# ChairControl.net
KiCad netlist of a schematic drawn in EAGLE
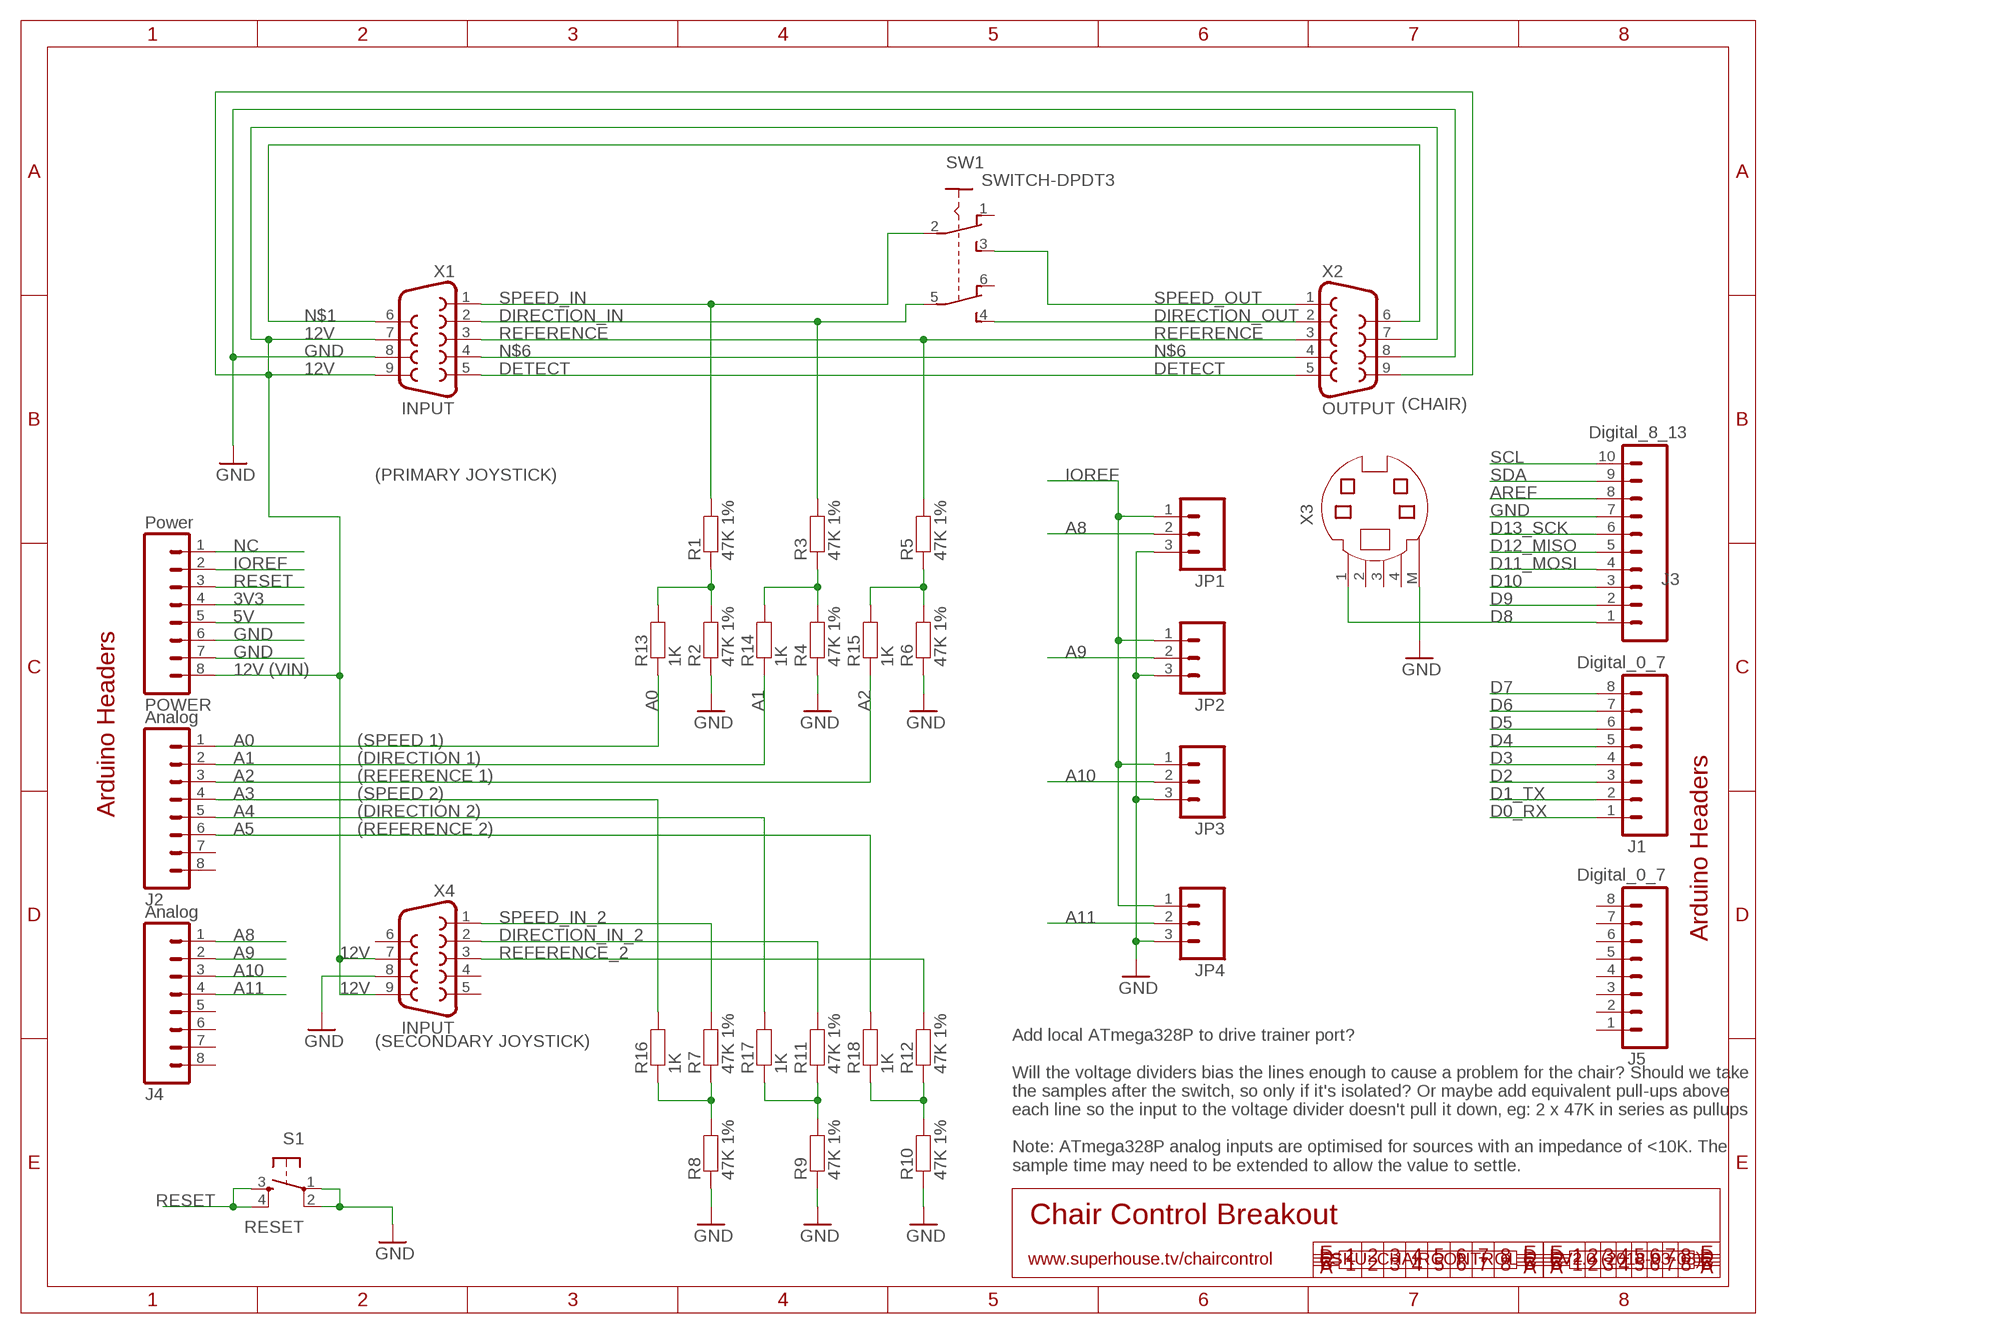
[diagram p0: schematic, sheet 1]

(export (version "E")
  (design (tool "Eeschema 10.0.6"))
  (components
    (comp (ref "J1")
      (value "Digital_0_7")
      (footprint "eagle-import:1X08")
      (libsource (lib "eagle-import") (part "M08"))
    )
    (comp (ref "J2")
      (value "Analog")
      (footprint "eagle-import:1X08")
      (libsource (lib "eagle-import") (part "M08PTH"))
    )
    (comp (ref "J3")
      (value "Digital_8_13")
      (footprint "eagle-import:1X10")
      (libsource (lib "eagle-import") (part "M100.1"))
    )
    (comp (ref "J4")
      (value "Analog")
      (footprint "eagle-import:1X08")
      (libsource (lib "eagle-import") (part "M08PTH"))
    )
    (comp (ref "J5")
      (value "Digital_0_7")
      (footprint "eagle-import:1X08")
      (libsource (lib "eagle-import") (part "M08"))
    )
    (comp (ref "JP1")
      (value "M03PTH")
      (footprint "eagle-import:1X03")
      (libsource (lib "eagle-import") (part "M03PTH"))
    )
    (comp (ref "JP2")
      (value "M03PTH")
      (footprint "eagle-import:1X03")
      (libsource (lib "eagle-import") (part "M03PTH"))
    )
    (comp (ref "JP3")
      (value "M03PTH")
      (footprint "eagle-import:1X03")
      (libsource (lib "eagle-import") (part "M03PTH"))
    )
    (comp (ref "JP4")
      (value "M03PTH")
      (footprint "eagle-import:1X03")
      (libsource (lib "eagle-import") (part "M03PTH"))
    )
    (comp (ref "POWER")
      (value "Power")
      (footprint "eagle-import:1X08")
      (libsource (lib "eagle-import") (part "freetronics-original_M08"))
    )
    (comp (ref "R1")
      (value "47K 1%")
      (footprint "eagle-import:0603")
      (libsource (lib "eagle-import") (part "RESISTOR0603"))
    )
    (comp (ref "R2")
      (value "47K 1%")
      (footprint "eagle-import:0603")
      (libsource (lib "eagle-import") (part "RESISTOR0603"))
    )
    (comp (ref "R3")
      (value "47K 1%")
      (footprint "eagle-import:0603")
      (libsource (lib "eagle-import") (part "RESISTOR0603"))
    )
    (comp (ref "R4")
      (value "47K 1%")
      (footprint "eagle-import:0603")
      (libsource (lib "eagle-import") (part "RESISTOR0603"))
    )
    (comp (ref "R5")
      (value "47K 1%")
      (footprint "eagle-import:0603")
      (libsource (lib "eagle-import") (part "RESISTOR0603"))
    )
    (comp (ref "R6")
      (value "47K 1%")
      (footprint "eagle-import:0603")
      (libsource (lib "eagle-import") (part "RESISTOR0603"))
    )
    (comp (ref "R7")
      (value "47K 1%")
      (footprint "eagle-import:0603")
      (libsource (lib "eagle-import") (part "RESISTOR0603"))
    )
    (comp (ref "R8")
      (value "47K 1%")
      (footprint "eagle-import:0603")
      (libsource (lib "eagle-import") (part "RESISTOR0603"))
    )
    (comp (ref "R9")
      (value "47K 1%")
      (footprint "eagle-import:0603")
      (libsource (lib "eagle-import") (part "RESISTOR0603"))
    )
    (comp (ref "R10")
      (value "47K 1%")
      (footprint "eagle-import:0603")
      (libsource (lib "eagle-import") (part "RESISTOR0603"))
    )
    (comp (ref "R11")
      (value "47K 1%")
      (footprint "eagle-import:0603")
      (libsource (lib "eagle-import") (part "RESISTOR0603"))
    )
    (comp (ref "R12")
      (value "47K 1%")
      (footprint "eagle-import:0603")
      (libsource (lib "eagle-import") (part "RESISTOR0603"))
    )
    (comp (ref "R13")
      (value "1K")
      (footprint "eagle-import:0603")
      (libsource (lib "eagle-import") (part "RESISTOR0603"))
    )
    (comp (ref "R14")
      (value "1K")
      (footprint "eagle-import:0603")
      (libsource (lib "eagle-import") (part "RESISTOR0603"))
    )
    (comp (ref "R15")
      (value "1K")
      (footprint "eagle-import:0603")
      (libsource (lib "eagle-import") (part "RESISTOR0603"))
    )
    (comp (ref "R16")
      (value "1K")
      (footprint "eagle-import:0603")
      (libsource (lib "eagle-import") (part "RESISTOR0603"))
    )
    (comp (ref "R17")
      (value "1K")
      (footprint "eagle-import:0603")
      (libsource (lib "eagle-import") (part "RESISTOR0603"))
    )
    (comp (ref "R18")
      (value "1K")
      (footprint "eagle-import:0603")
      (libsource (lib "eagle-import") (part "RESISTOR0603"))
    )
    (comp (ref "S1")
      (value "RESET")
      (footprint "eagle-import:TACTILE-PTH")
      (libsource (lib "eagle-import") (part "TAC_SWITCHPTH"))
    )
    (comp (ref "SW1")
      (value "SWITCH-DPDT3")
      (footprint "eagle-import:7201SD9AV2BE")
      (libsource (lib "eagle-import") (part "SWITCH-DPDT3"))
    )
    (comp (ref "X1")
      (value "INPUT")
      (footprint "eagle-import:DB9_MALE")
      (libsource (lib "eagle-import") (part "DB9MALE"))
    )
    (comp (ref "X2")
      (value "OUTPUT")
      (footprint "eagle-import:DB9")
      (libsource (lib "eagle-import") (part "DB9FEMALE"))
    )
    (comp (ref "X3")
      (value "MD04S")
      (footprint "eagle-import:MDIN04S")
      (libsource (lib "eagle-import") (part "MD04S"))
    )
    (comp (ref "X4")
      (value "INPUT")
      (footprint "eagle-import:DB9_MALE")
      (libsource (lib "eagle-import") (part "DB9MALE"))
    )
  )
  (nets
    (net (code "1") (name "/3V3") (class "Default")
      (node (ref "POWER") (pin "4") (pinfunction "4_4") (pintype "passive"))
    )
    (net (code "2") (name "/5V") (class "Default")
      (node (ref "POWER") (pin "5") (pinfunction "5_5") (pintype "passive"))
    )
    (net (code "3") (name "/12V") (class "Default")
      (node (ref "POWER") (pin "8") (pinfunction "8_8") (pintype "passive"))
      (node (ref "X1") (pin "7") (pinfunction "7_7") (pintype "passive"))
      (node (ref "X1") (pin "9") (pinfunction "9_9") (pintype "passive"))
      (node (ref "X2") (pin "7") (pinfunction "7_7") (pintype "passive"))
      (node (ref "X2") (pin "9") (pinfunction "9_9") (pintype "passive"))
      (node (ref "X4") (pin "7") (pinfunction "7_7") (pintype "passive"))
      (node (ref "X4") (pin "9") (pinfunction "9_9") (pintype "passive"))
    )
    (net (code "4") (name "/A0") (class "Default")
      (node (ref "J2") (pin "1") (pinfunction "1_1") (pintype "passive"))
      (node (ref "R13") (pin "1") (pinfunction "1_1") (pintype "passive"))
    )
    (net (code "5") (name "/A1") (class "Default")
      (node (ref "J2") (pin "2") (pinfunction "2_2") (pintype "passive"))
      (node (ref "R14") (pin "1") (pinfunction "1_1") (pintype "passive"))
    )
    (net (code "6") (name "/A2") (class "Default")
      (node (ref "J2") (pin "3") (pinfunction "3_3") (pintype "passive"))
      (node (ref "R15") (pin "1") (pinfunction "1_1") (pintype "passive"))
    )
    (net (code "7") (name "/A3") (class "Default")
      (node (ref "J2") (pin "4") (pinfunction "4_4") (pintype "passive"))
      (node (ref "R16") (pin "2") (pinfunction "2_2") (pintype "passive"))
    )
    (net (code "8") (name "/A4") (class "Default")
      (node (ref "J2") (pin "5") (pinfunction "5_5") (pintype "passive"))
      (node (ref "R17") (pin "2") (pinfunction "2_2") (pintype "passive"))
    )
    (net (code "9") (name "/A5") (class "Default")
      (node (ref "J2") (pin "6") (pinfunction "6_6") (pintype "passive"))
      (node (ref "R18") (pin "2") (pinfunction "2_2") (pintype "passive"))
    )
    (net (code "10") (name "/A8") (class "Default")
      (node (ref "J4") (pin "1") (pinfunction "1_1") (pintype "passive"))
      (node (ref "JP1") (pin "2") (pinfunction "2_2") (pintype "passive"))
    )
    (net (code "11") (name "/A9") (class "Default")
      (node (ref "J4") (pin "2") (pinfunction "2_2") (pintype "passive"))
      (node (ref "JP2") (pin "2") (pinfunction "2_2") (pintype "passive"))
    )
    (net (code "12") (name "/A10") (class "Default")
      (node (ref "J4") (pin "3") (pinfunction "3_3") (pintype "passive"))
      (node (ref "JP3") (pin "2") (pinfunction "2_2") (pintype "passive"))
    )
    (net (code "13") (name "/A11") (class "Default")
      (node (ref "J4") (pin "4") (pinfunction "4_4") (pintype "passive"))
      (node (ref "JP4") (pin "2") (pinfunction "2_2") (pintype "passive"))
    )
    (net (code "14") (name "/AREF") (class "Default")
      (node (ref "J3") (pin "8") (pinfunction "8_8") (pintype "passive"))
    )
    (net (code "15") (name "/D0_RX") (class "Default")
      (node (ref "J1") (pin "1") (pinfunction "1_1") (pintype "passive"))
    )
    (net (code "16") (name "/D1_TX") (class "Default")
      (node (ref "J1") (pin "2") (pinfunction "2_2") (pintype "passive"))
    )
    (net (code "17") (name "/D2") (class "Default")
      (node (ref "J1") (pin "3") (pinfunction "3_3") (pintype "passive"))
    )
    (net (code "18") (name "/D3") (class "Default")
      (node (ref "J1") (pin "4") (pinfunction "4_4") (pintype "passive"))
    )
    (net (code "19") (name "/D4") (class "Default")
      (node (ref "J1") (pin "5") (pinfunction "5_5") (pintype "passive"))
    )
    (net (code "20") (name "/D5") (class "Default")
      (node (ref "J1") (pin "6") (pinfunction "6_6") (pintype "passive"))
    )
    (net (code "21") (name "/D6") (class "Default")
      (node (ref "J1") (pin "7") (pinfunction "7_7") (pintype "passive"))
    )
    (net (code "22") (name "/D7") (class "Default")
      (node (ref "J1") (pin "8") (pinfunction "8_8") (pintype "passive"))
    )
    (net (code "23") (name "/D8") (class "Default")
      (node (ref "J3") (pin "1") (pinfunction "1_1") (pintype "passive"))
      (node (ref "X3") (pin "1") (pinfunction "1_1") (pintype "passive"))
    )
    (net (code "24") (name "/D9") (class "Default")
      (node (ref "J3") (pin "2") (pinfunction "2_2") (pintype "passive"))
    )
    (net (code "25") (name "/D10") (class "Default")
      (node (ref "J3") (pin "3") (pinfunction "3_3") (pintype "passive"))
    )
    (net (code "26") (name "/D11_MOSI") (class "Default")
      (node (ref "J3") (pin "4") (pinfunction "4_4") (pintype "passive"))
    )
    (net (code "27") (name "/D12_MISO") (class "Default")
      (node (ref "J3") (pin "5") (pinfunction "5_5") (pintype "passive"))
    )
    (net (code "28") (name "/D13_SCK") (class "Default")
      (node (ref "J3") (pin "6") (pinfunction "6_6") (pintype "passive"))
    )
    (net (code "29") (name "/DETECT") (class "Default")
      (node (ref "X1") (pin "5") (pinfunction "5_5") (pintype "passive"))
      (node (ref "X2") (pin "5") (pinfunction "5_5") (pintype "passive"))
    )
    (net (code "30") (name "/DIRECTION_IN") (class "Default")
      (node (ref "R3") (pin "2") (pinfunction "2_2") (pintype "passive"))
      (node (ref "SW1") (pin "5") (pinfunction "5_5") (pintype "passive"))
      (node (ref "X1") (pin "2") (pinfunction "2_2") (pintype "passive"))
    )
    (net (code "31") (name "/DIRECTION_IN_2") (class "Default")
      (node (ref "R11") (pin "2") (pinfunction "2_2") (pintype "passive"))
      (node (ref "X4") (pin "2") (pinfunction "2_2") (pintype "passive"))
    )
    (net (code "32") (name "/DIRECTION_OUT") (class "Default")
      (node (ref "SW1") (pin "4") (pinfunction "4_4") (pintype "passive"))
      (node (ref "X2") (pin "2") (pinfunction "2_2") (pintype "passive"))
    )
    (net (code "33") (name "/IOREF") (class "Default")
      (node (ref "JP1") (pin "1") (pinfunction "1_1") (pintype "passive"))
      (node (ref "JP2") (pin "1") (pinfunction "1_1") (pintype "passive"))
      (node (ref "JP3") (pin "1") (pinfunction "1_1") (pintype "passive"))
      (node (ref "JP4") (pin "1") (pinfunction "1_1") (pintype "passive"))
      (node (ref "POWER") (pin "2") (pinfunction "2_2") (pintype "passive"))
    )
    (net (code "34") (name "/N$1") (class "Default")
      (node (ref "X1") (pin "6") (pinfunction "6_6") (pintype "passive"))
      (node (ref "X2") (pin "6") (pinfunction "6_6") (pintype "passive"))
    )
    (net (code "35") (name "/N$6") (class "Default")
      (node (ref "X1") (pin "4") (pinfunction "4_4") (pintype "passive"))
      (node (ref "X2") (pin "4") (pinfunction "4_4") (pintype "passive"))
    )
    (net (code "36") (name "/NC") (class "Default")
      (node (ref "POWER") (pin "1") (pinfunction "1_1") (pintype "passive"))
    )
    (net (code "37") (name "/REFERENCE") (class "Default")
      (node (ref "R5") (pin "2") (pinfunction "2_2") (pintype "passive"))
      (node (ref "X1") (pin "3") (pinfunction "3_3") (pintype "passive"))
      (node (ref "X2") (pin "3") (pinfunction "3_3") (pintype "passive"))
    )
    (net (code "38") (name "/REFERENCE_2") (class "Default")
      (node (ref "R12") (pin "2") (pinfunction "2_2") (pintype "passive"))
      (node (ref "X4") (pin "3") (pinfunction "3_3") (pintype "passive"))
    )
    (net (code "39") (name "/RESET") (class "Default")
      (node (ref "POWER") (pin "3") (pinfunction "3_3") (pintype "passive"))
      (node (ref "S1") (pin "3") (pinfunction "3_3") (pintype "passive"))
      (node (ref "S1") (pin "4") (pinfunction "4_4") (pintype "passive"))
    )
    (net (code "40") (name "/SCL") (class "Default")
      (node (ref "J3") (pin "10") (pinfunction "10_10") (pintype "passive"))
    )
    (net (code "41") (name "/SDA") (class "Default")
      (node (ref "J3") (pin "9") (pinfunction "9_9") (pintype "passive"))
    )
    (net (code "42") (name "/SPEED_IN") (class "Default")
      (node (ref "R1") (pin "2") (pinfunction "2_2") (pintype "passive"))
      (node (ref "SW1") (pin "2") (pinfunction "2_2") (pintype "passive"))
      (node (ref "X1") (pin "1") (pinfunction "1_1") (pintype "passive"))
    )
    (net (code "43") (name "/SPEED_IN_2") (class "Default")
      (node (ref "R7") (pin "2") (pinfunction "2_2") (pintype "passive"))
      (node (ref "X4") (pin "1") (pinfunction "1_1") (pintype "passive"))
    )
    (net (code "44") (name "/SPEED_OUT") (class "Default")
      (node (ref "SW1") (pin "3") (pinfunction "3_3") (pintype "passive"))
      (node (ref "X2") (pin "1") (pinfunction "1_1") (pintype "passive"))
    )
    (net (code "45") (name "GND") (class "Default")
      (node (ref "J3") (pin "7") (pinfunction "7_7") (pintype "passive"))
      (node (ref "JP1") (pin "3") (pinfunction "3_3") (pintype "passive"))
      (node (ref "JP2") (pin "3") (pinfunction "3_3") (pintype "passive"))
      (node (ref "JP3") (pin "3") (pinfunction "3_3") (pintype "passive"))
      (node (ref "JP4") (pin "3") (pinfunction "3_3") (pintype "passive"))
      (node (ref "POWER") (pin "6") (pinfunction "6_6") (pintype "passive"))
      (node (ref "POWER") (pin "7") (pinfunction "7_7") (pintype "passive"))
      (node (ref "R10") (pin "1") (pinfunction "1_1") (pintype "passive"))
      (node (ref "R2") (pin "1") (pinfunction "1_1") (pintype "passive"))
      (node (ref "R4") (pin "1") (pinfunction "1_1") (pintype "passive"))
      (node (ref "R6") (pin "1") (pinfunction "1_1") (pintype "passive"))
      (node (ref "R8") (pin "1") (pinfunction "1_1") (pintype "passive"))
      (node (ref "R9") (pin "1") (pinfunction "1_1") (pintype "passive"))
      (node (ref "S1") (pin "1") (pinfunction "1_1") (pintype "passive"))
      (node (ref "S1") (pin "2") (pinfunction "2_2") (pintype "passive"))
      (node (ref "X1") (pin "8") (pinfunction "8_8") (pintype "passive"))
      (node (ref "X2") (pin "8") (pinfunction "8_8") (pintype "passive"))
      (node (ref "X3") (pin "M") (pinfunction "5_M") (pintype "passive"))
      (node (ref "X4") (pin "8") (pinfunction "8_8") (pintype "passive"))
    )
    (net (code "46") (name "Net-(R1-Pad1)") (class "Default")
      (node (ref "R1") (pin "1") (pinfunction "1_1") (pintype "passive"))
      (node (ref "R13") (pin "2") (pinfunction "2_2") (pintype "passive"))
      (node (ref "R2") (pin "2") (pinfunction "2_2") (pintype "passive"))
    )
    (net (code "47") (name "Net-(R10-Pad2)") (class "Default")
      (node (ref "R10") (pin "2") (pinfunction "2_2") (pintype "passive"))
      (node (ref "R12") (pin "1") (pinfunction "1_1") (pintype "passive"))
      (node (ref "R18") (pin "1") (pinfunction "1_1") (pintype "passive"))
    )
    (net (code "48") (name "Net-(R11-Pad1)") (class "Default")
      (node (ref "R11") (pin "1") (pinfunction "1_1") (pintype "passive"))
      (node (ref "R17") (pin "1") (pinfunction "1_1") (pintype "passive"))
      (node (ref "R9") (pin "2") (pinfunction "2_2") (pintype "passive"))
    )
    (net (code "49") (name "Net-(R14-Pad2)") (class "Default")
      (node (ref "R14") (pin "2") (pinfunction "2_2") (pintype "passive"))
      (node (ref "R3") (pin "1") (pinfunction "1_1") (pintype "passive"))
      (node (ref "R4") (pin "2") (pinfunction "2_2") (pintype "passive"))
    )
    (net (code "50") (name "Net-(R15-Pad2)") (class "Default")
      (node (ref "R15") (pin "2") (pinfunction "2_2") (pintype "passive"))
      (node (ref "R5") (pin "1") (pinfunction "1_1") (pintype "passive"))
      (node (ref "R6") (pin "2") (pinfunction "2_2") (pintype "passive"))
    )
    (net (code "51") (name "Net-(R16-Pad1)") (class "Default")
      (node (ref "R16") (pin "1") (pinfunction "1_1") (pintype "passive"))
      (node (ref "R7") (pin "1") (pinfunction "1_1") (pintype "passive"))
      (node (ref "R8") (pin "2") (pinfunction "2_2") (pintype "passive"))
    )
    (net (code "52") (name "unconnected-(J2-Pad7)") (class "Default")
      (node (ref "J2") (pin "7") (pinfunction "7_7") (pintype "passive"))
    )
    (net (code "53") (name "unconnected-(J2-Pad8)") (class "Default")
      (node (ref "J2") (pin "8") (pinfunction "8_8") (pintype "passive"))
    )
    (net (code "54") (name "unconnected-(J4-Pad5)") (class "Default")
      (node (ref "J4") (pin "5") (pinfunction "5_5") (pintype "passive"))
    )
    (net (code "55") (name "unconnected-(J4-Pad6)") (class "Default")
      (node (ref "J4") (pin "6") (pinfunction "6_6") (pintype "passive"))
    )
    (net (code "56") (name "unconnected-(J4-Pad7)") (class "Default")
      (node (ref "J4") (pin "7") (pinfunction "7_7") (pintype "passive"))
    )
    (net (code "57") (name "unconnected-(J4-Pad8)") (class "Default")
      (node (ref "J4") (pin "8") (pinfunction "8_8") (pintype "passive"))
    )
    (net (code "58") (name "unconnected-(J5-Pad1)") (class "Default")
      (node (ref "J5") (pin "1") (pinfunction "1_1") (pintype "passive"))
    )
    (net (code "59") (name "unconnected-(J5-Pad2)") (class "Default")
      (node (ref "J5") (pin "2") (pinfunction "2_2") (pintype "passive"))
    )
    (net (code "60") (name "unconnected-(J5-Pad3)") (class "Default")
      (node (ref "J5") (pin "3") (pinfunction "3_3") (pintype "passive"))
    )
    (net (code "61") (name "unconnected-(J5-Pad4)") (class "Default")
      (node (ref "J5") (pin "4") (pinfunction "4_4") (pintype "passive"))
    )
    (net (code "62") (name "unconnected-(J5-Pad5)") (class "Default")
      (node (ref "J5") (pin "5") (pinfunction "5_5") (pintype "passive"))
    )
    (net (code "63") (name "unconnected-(J5-Pad6)") (class "Default")
      (node (ref "J5") (pin "6") (pinfunction "6_6") (pintype "passive"))
    )
    (net (code "64") (name "unconnected-(J5-Pad7)") (class "Default")
      (node (ref "J5") (pin "7") (pinfunction "7_7") (pintype "passive"))
    )
    (net (code "65") (name "unconnected-(J5-Pad8)") (class "Default")
      (node (ref "J5") (pin "8") (pinfunction "8_8") (pintype "passive"))
    )
    (net (code "66") (name "unconnected-(SW1-Pad1)") (class "Default")
      (node (ref "SW1") (pin "1") (pinfunction "1_1") (pintype "passive"))
    )
    (net (code "67") (name "unconnected-(SW1-Pad6)") (class "Default")
      (node (ref "SW1") (pin "6") (pinfunction "6_6") (pintype "passive"))
    )
    (net (code "68") (name "unconnected-(X3-Pad2)") (class "Default")
      (node (ref "X3") (pin "2") (pinfunction "2_2") (pintype "passive"))
    )
    (net (code "69") (name "unconnected-(X3-Pad3)") (class "Default")
      (node (ref "X3") (pin "3") (pinfunction "3_3") (pintype "passive"))
    )
    (net (code "70") (name "unconnected-(X3-Pad4)") (class "Default")
      (node (ref "X3") (pin "4") (pinfunction "4_4") (pintype "passive"))
    )
    (net (code "71") (name "unconnected-(X4-Pad4)") (class "Default")
      (node (ref "X4") (pin "4") (pinfunction "4_4") (pintype "passive"))
    )
    (net (code "72") (name "unconnected-(X4-Pad5)") (class "Default")
      (node (ref "X4") (pin "5") (pinfunction "5_5") (pintype "passive"))
    )
    (net (code "73") (name "unconnected-(X4-Pad6)") (class "Default")
      (node (ref "X4") (pin "6") (pinfunction "6_6") (pintype "passive"))
    )
  )
)
